# ATtiny20_Study_-_UFBGA15.net
KiCad netlist of a schematic drawn in EAGLE
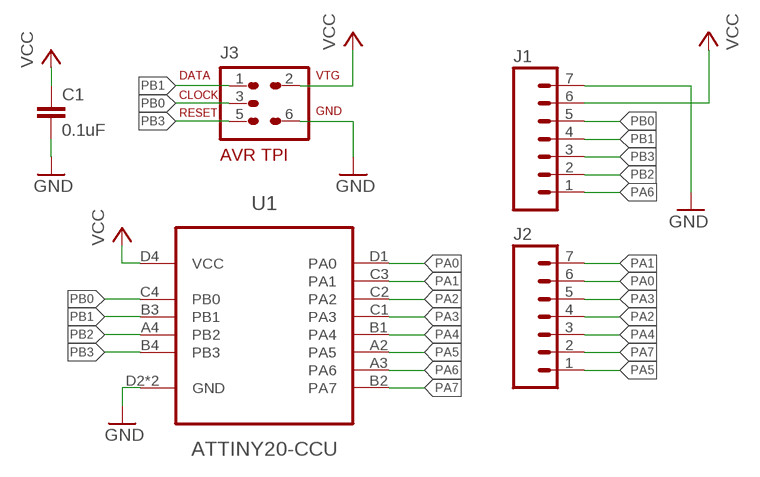
[diagram p0: schematic, sheet 1]

(export (version "E")
  (design (tool "Eeschema 10.0.6"))
  (components
    (comp (ref "C1")
      (value "0.1uF")
      (footprint "eagle-import:0402-CAP")
      (libsource (lib "eagle-import") (part "CAP0402-CAP"))
    )
    (comp (ref "J1")
      (value "M07")
      (footprint "eagle-import:1X07")
      (libsource (lib "eagle-import") (part "M07"))
    )
    (comp (ref "J2")
      (value "M07")
      (footprint "eagle-import:1X07")
      (libsource (lib "eagle-import") (part "M07"))
    )
    (comp (ref "J3")
      (value "AVR-TPIVERT")
      (footprint "eagle-import:AVR-ISP-6")
      (libsource (lib "eagle-import") (part "AVR-TPIVERT"))
    )
    (comp (ref "U1")
      (value "ATTINY20-CCU")
      (footprint "eagle-import:15CC1")
      (libsource (lib "eagle-import") (part "ATTINY20-CCU"))
    )
  )
  (nets
    (net (code "1") (name "GND") (class "Default")
      (node (ref "C1") (pin "2") (pinfunction "2_2") (pintype "passive"))
      (node (ref "J1") (pin "7") (pinfunction "7_7") (pintype "passive"))
      (node (ref "J3") (pin "6") (pinfunction "6_6") (pintype "passive"))
      (node (ref "U1") (pin "D2") (pinfunction "GND_D2") (pintype "passive"))
      (node (ref "U1") (pin "D3") (pinfunction "GND_D3") (pintype "passive"))
    )
    (net (code "2") (name "PA0") (class "Default")
      (node (ref "J2") (pin "6") (pinfunction "6_6") (pintype "passive"))
      (node (ref "U1") (pin "D1") (pinfunction "PA0_D1") (pintype "bidirectional"))
    )
    (net (code "3") (name "PA1") (class "Default")
      (node (ref "J2") (pin "7") (pinfunction "7_7") (pintype "passive"))
      (node (ref "U1") (pin "C3") (pinfunction "PA1_C3") (pintype "bidirectional"))
    )
    (net (code "4") (name "PA2") (class "Default")
      (node (ref "J2") (pin "4") (pinfunction "4_4") (pintype "passive"))
      (node (ref "U1") (pin "C2") (pinfunction "PA2_C2") (pintype "bidirectional"))
    )
    (net (code "5") (name "PA3") (class "Default")
      (node (ref "J2") (pin "5") (pinfunction "5_5") (pintype "passive"))
      (node (ref "U1") (pin "C1") (pinfunction "PA3_C1") (pintype "bidirectional"))
    )
    (net (code "6") (name "PA4") (class "Default")
      (node (ref "J2") (pin "3") (pinfunction "3_3") (pintype "passive"))
      (node (ref "U1") (pin "B1") (pinfunction "PA4_B1") (pintype "bidirectional"))
    )
    (net (code "7") (name "PA5") (class "Default")
      (node (ref "J2") (pin "1") (pinfunction "1_1") (pintype "passive"))
      (node (ref "U1") (pin "A2") (pinfunction "PA5_A2") (pintype "bidirectional"))
    )
    (net (code "8") (name "PA6") (class "Default")
      (node (ref "J1") (pin "1") (pinfunction "1_1") (pintype "passive"))
      (node (ref "U1") (pin "A3") (pinfunction "PA6_A3") (pintype "bidirectional"))
    )
    (net (code "9") (name "PA7") (class "Default")
      (node (ref "J2") (pin "2") (pinfunction "2_2") (pintype "passive"))
      (node (ref "U1") (pin "B2") (pinfunction "PA7_B2") (pintype "bidirectional"))
    )
    (net (code "10") (name "PB0") (class "Default")
      (node (ref "J1") (pin "5") (pinfunction "5_5") (pintype "passive"))
      (node (ref "J3") (pin "3") (pinfunction "3_3") (pintype "passive"))
      (node (ref "U1") (pin "C4") (pinfunction "PB0_C4") (pintype "bidirectional"))
    )
    (net (code "11") (name "PB1") (class "Default")
      (node (ref "J1") (pin "4") (pinfunction "4_4") (pintype "passive"))
      (node (ref "J3") (pin "1") (pinfunction "1_1") (pintype "passive"))
      (node (ref "U1") (pin "B3") (pinfunction "PB1_B3") (pintype "bidirectional"))
    )
    (net (code "12") (name "PB2") (class "Default")
      (node (ref "J1") (pin "2") (pinfunction "2_2") (pintype "passive"))
      (node (ref "U1") (pin "A4") (pinfunction "PB2_A4") (pintype "bidirectional"))
    )
    (net (code "13") (name "PB3") (class "Default")
      (node (ref "J1") (pin "3") (pinfunction "3_3") (pintype "passive"))
      (node (ref "J3") (pin "5") (pinfunction "5_5") (pintype "passive"))
      (node (ref "U1") (pin "B4") (pinfunction "PB3_B4") (pintype "bidirectional"))
    )
    (net (code "14") (name "VCC") (class "Default")
      (node (ref "C1") (pin "1") (pinfunction "1_1") (pintype "passive"))
      (node (ref "J1") (pin "6") (pinfunction "6_6") (pintype "passive"))
      (node (ref "J3") (pin "2") (pinfunction "2_2") (pintype "passive"))
      (node (ref "U1") (pin "D4") (pinfunction "VCC_D4") (pintype "power_in"))
    )
  )
)
